# capactive_hub.net
KiCad netlist of a schematic drawn in EAGLE
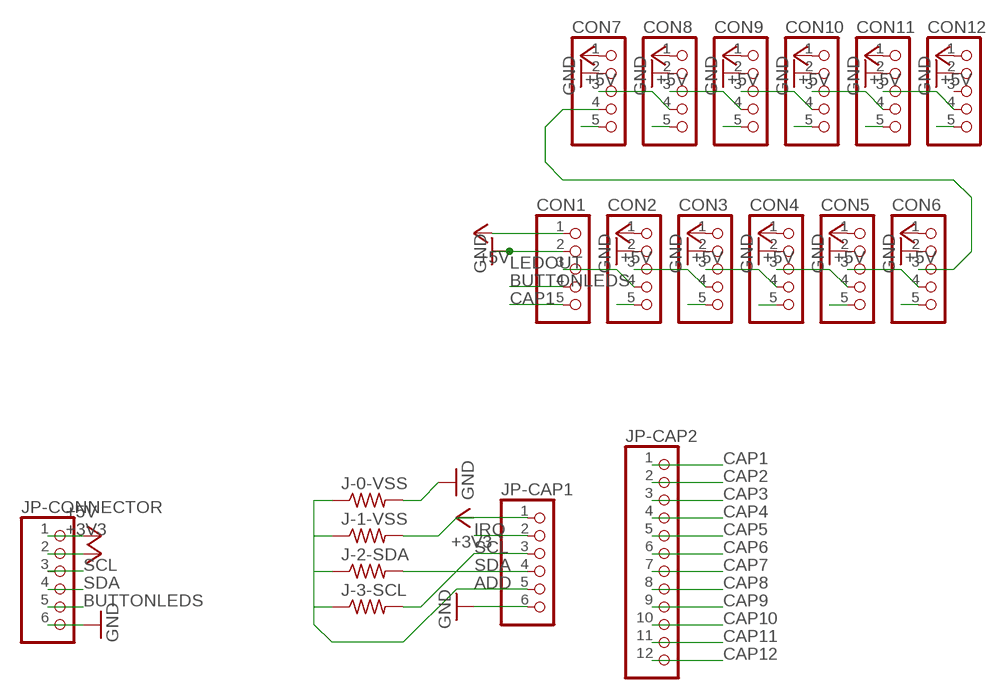
[diagram p0: schematic, sheet 1]

(export (version "E")
  (design (tool "Eeschema 10.0.6"))
  (components
    (comp (ref "CON1")
      (value "PINHD-1X5")
      (footprint "eagle-import:1X05")
      (libsource (lib "eagle-import") (part "PINHD-1X5"))
    )
    (comp (ref "CON2")
      (value "PINHD-1X5")
      (footprint "eagle-import:1X05")
      (libsource (lib "eagle-import") (part "PINHD-1X5"))
    )
    (comp (ref "CON3")
      (value "PINHD-1X5")
      (footprint "eagle-import:1X05")
      (libsource (lib "eagle-import") (part "PINHD-1X5"))
    )
    (comp (ref "CON4")
      (value "PINHD-1X5")
      (footprint "eagle-import:1X05")
      (libsource (lib "eagle-import") (part "PINHD-1X5"))
    )
    (comp (ref "CON5")
      (value "PINHD-1X5")
      (footprint "eagle-import:1X05")
      (libsource (lib "eagle-import") (part "PINHD-1X5"))
    )
    (comp (ref "CON6")
      (value "PINHD-1X5")
      (footprint "eagle-import:1X05")
      (libsource (lib "eagle-import") (part "PINHD-1X5"))
    )
    (comp (ref "CON7")
      (value "PINHD-1X5")
      (footprint "eagle-import:1X05")
      (libsource (lib "eagle-import") (part "PINHD-1X5"))
    )
    (comp (ref "CON8")
      (value "PINHD-1X5")
      (footprint "eagle-import:1X05")
      (libsource (lib "eagle-import") (part "PINHD-1X5"))
    )
    (comp (ref "CON9")
      (value "PINHD-1X5")
      (footprint "eagle-import:1X05")
      (libsource (lib "eagle-import") (part "PINHD-1X5"))
    )
    (comp (ref "CON10")
      (value "PINHD-1X5")
      (footprint "eagle-import:1X05")
      (libsource (lib "eagle-import") (part "PINHD-1X5"))
    )
    (comp (ref "CON11")
      (value "PINHD-1X5")
      (footprint "eagle-import:1X05")
      (libsource (lib "eagle-import") (part "PINHD-1X5"))
    )
    (comp (ref "CON12")
      (value "PINHD-1X5")
      (footprint "eagle-import:1X05")
      (libsource (lib "eagle-import") (part "PINHD-1X5"))
    )
    (comp (ref "J-0-VSS")
      (value "RES-US1206FAB")
      (footprint "eagle-import:R1206FAB")
      (libsource (lib "eagle-import") (part "RES-US1206FAB"))
    )
    (comp (ref "J-1-VSS")
      (value "RES-US1206FAB")
      (footprint "eagle-import:R1206FAB")
      (libsource (lib "eagle-import") (part "RES-US1206FAB"))
    )
    (comp (ref "J-2-SDA")
      (value "RES-US1206FAB")
      (footprint "eagle-import:R1206FAB")
      (libsource (lib "eagle-import") (part "RES-US1206FAB"))
    )
    (comp (ref "J-3-SCL")
      (value "RES-US1206FAB")
      (footprint "eagle-import:R1206FAB")
      (libsource (lib "eagle-import") (part "RES-US1206FAB"))
    )
    (comp (ref "JP-CAP1")
      (value "PINHD-1X6")
      (footprint "eagle-import:1X06")
      (libsource (lib "eagle-import") (part "PINHD-1X6"))
    )
    (comp (ref "JP-CAP2")
      (value "PINHD-1X12")
      (footprint "eagle-import:1X12")
      (libsource (lib "eagle-import") (part "PINHD-1X12"))
    )
    (comp (ref "JP-CONNECTOR")
      (value "PINHD-1X6")
      (footprint "eagle-import:1X06")
      (libsource (lib "eagle-import") (part "PINHD-1X6"))
    )
  )
  (nets
    (net (code "1") (name "+3V3") (class "Default")
      (node (ref "J-1-VSS") (pin "2") (pinfunction "2_2") (pintype "passive"))
      (node (ref "JP-CAP1") (pin "1") (pinfunction "1_1") (pintype "passive"))
      (node (ref "JP-CONNECTOR") (pin "2") (pinfunction "2_2") (pintype "passive"))
    )
    (net (code "2") (name "+5V") (class "Default")
      (node (ref "CON1") (pin "1") (pinfunction "1_1") (pintype "passive"))
      (node (ref "CON10") (pin "1") (pinfunction "1_1") (pintype "passive"))
      (node (ref "CON11") (pin "1") (pinfunction "1_1") (pintype "passive"))
      (node (ref "CON12") (pin "1") (pinfunction "1_1") (pintype "passive"))
      (node (ref "CON2") (pin "1") (pinfunction "1_1") (pintype "passive"))
      (node (ref "CON3") (pin "1") (pinfunction "1_1") (pintype "passive"))
      (node (ref "CON4") (pin "1") (pinfunction "1_1") (pintype "passive"))
      (node (ref "CON5") (pin "1") (pinfunction "1_1") (pintype "passive"))
      (node (ref "CON6") (pin "1") (pinfunction "1_1") (pintype "passive"))
      (node (ref "CON7") (pin "1") (pinfunction "1_1") (pintype "passive"))
      (node (ref "CON8") (pin "1") (pinfunction "1_1") (pintype "passive"))
      (node (ref "CON9") (pin "1") (pinfunction "1_1") (pintype "passive"))
      (node (ref "JP-CONNECTOR") (pin "1") (pinfunction "1_1") (pintype "passive"))
    )
    (net (code "3") (name "/ADD") (class "Default")
      (node (ref "J-0-VSS") (pin "1") (pinfunction "1_1") (pintype "passive"))
      (node (ref "J-1-VSS") (pin "1") (pinfunction "1_1") (pintype "passive"))
      (node (ref "J-2-SDA") (pin "1") (pinfunction "1_1") (pintype "passive"))
      (node (ref "J-3-SCL") (pin "1") (pinfunction "1_1") (pintype "passive"))
      (node (ref "JP-CAP1") (pin "5") (pinfunction "5_5") (pintype "passive"))
    )
    (net (code "4") (name "/BUTTONLEDS") (class "Default")
      (node (ref "CON1") (pin "4") (pinfunction "4_4") (pintype "passive"))
      (node (ref "JP-CONNECTOR") (pin "5") (pinfunction "5_5") (pintype "passive"))
    )
    (net (code "5") (name "/CAP1") (class "Default")
      (node (ref "CON1") (pin "5") (pinfunction "5_5") (pintype "passive"))
      (node (ref "JP-CAP2") (pin "1") (pinfunction "1_1") (pintype "passive"))
    )
    (net (code "6") (name "/CAP2") (class "Default")
      (node (ref "CON2") (pin "5") (pinfunction "5_5") (pintype "passive"))
      (node (ref "JP-CAP2") (pin "2") (pinfunction "2_2") (pintype "passive"))
    )
    (net (code "7") (name "/CAP3") (class "Default")
      (node (ref "CON3") (pin "5") (pinfunction "5_5") (pintype "passive"))
      (node (ref "JP-CAP2") (pin "3") (pinfunction "3_3") (pintype "passive"))
    )
    (net (code "8") (name "/CAP4") (class "Default")
      (node (ref "CON4") (pin "5") (pinfunction "5_5") (pintype "passive"))
      (node (ref "JP-CAP2") (pin "4") (pinfunction "4_4") (pintype "passive"))
    )
    (net (code "9") (name "/CAP5") (class "Default")
      (node (ref "CON5") (pin "5") (pinfunction "5_5") (pintype "passive"))
      (node (ref "JP-CAP2") (pin "5") (pinfunction "5_5") (pintype "passive"))
    )
    (net (code "10") (name "/CAP6") (class "Default")
      (node (ref "CON6") (pin "5") (pinfunction "5_5") (pintype "passive"))
      (node (ref "JP-CAP2") (pin "6") (pinfunction "6_6") (pintype "passive"))
    )
    (net (code "11") (name "/CAP7") (class "Default")
      (node (ref "CON7") (pin "5") (pinfunction "5_5") (pintype "passive"))
      (node (ref "JP-CAP2") (pin "7") (pinfunction "7_7") (pintype "passive"))
    )
    (net (code "12") (name "/CAP8") (class "Default")
      (node (ref "CON8") (pin "5") (pinfunction "5_5") (pintype "passive"))
      (node (ref "JP-CAP2") (pin "8") (pinfunction "8_8") (pintype "passive"))
    )
    (net (code "13") (name "/CAP9") (class "Default")
      (node (ref "CON9") (pin "5") (pinfunction "5_5") (pintype "passive"))
      (node (ref "JP-CAP2") (pin "9") (pinfunction "9_9") (pintype "passive"))
    )
    (net (code "14") (name "/CAP10") (class "Default")
      (node (ref "CON10") (pin "5") (pinfunction "5_5") (pintype "passive"))
      (node (ref "JP-CAP2") (pin "10") (pinfunction "10_10") (pintype "passive"))
    )
    (net (code "15") (name "/CAP11") (class "Default")
      (node (ref "CON11") (pin "5") (pinfunction "5_5") (pintype "passive"))
      (node (ref "JP-CAP2") (pin "11") (pinfunction "11_11") (pintype "passive"))
    )
    (net (code "16") (name "/CAP12") (class "Default")
      (node (ref "CON12") (pin "5") (pinfunction "5_5") (pintype "passive"))
      (node (ref "JP-CAP2") (pin "12") (pinfunction "12_12") (pintype "passive"))
    )
    (net (code "17") (name "/IRQ") (class "Default")
      (node (ref "JP-CAP1") (pin "2") (pinfunction "2_2") (pintype "passive"))
    )
    (net (code "18") (name "/LEDOUT") (class "Default")
      (node (ref "CON1") (pin "3") (pinfunction "3_3") (pintype "passive"))
      (node (ref "CON2") (pin "4") (pinfunction "4_4") (pintype "passive"))
    )
    (net (code "19") (name "/SCL") (class "Default")
      (node (ref "J-3-SCL") (pin "2") (pinfunction "2_2") (pintype "passive"))
      (node (ref "JP-CAP1") (pin "3") (pinfunction "3_3") (pintype "passive"))
      (node (ref "JP-CONNECTOR") (pin "3") (pinfunction "3_3") (pintype "passive"))
    )
    (net (code "20") (name "/SDA") (class "Default")
      (node (ref "J-2-SDA") (pin "2") (pinfunction "2_2") (pintype "passive"))
      (node (ref "JP-CAP1") (pin "4") (pinfunction "4_4") (pintype "passive"))
      (node (ref "JP-CONNECTOR") (pin "4") (pinfunction "4_4") (pintype "passive"))
    )
    (net (code "21") (name "GND") (class "Default")
      (node (ref "CON1") (pin "2") (pinfunction "2_2") (pintype "passive"))
      (node (ref "CON10") (pin "2") (pinfunction "2_2") (pintype "passive"))
      (node (ref "CON11") (pin "2") (pinfunction "2_2") (pintype "passive"))
      (node (ref "CON12") (pin "2") (pinfunction "2_2") (pintype "passive"))
      (node (ref "CON2") (pin "2") (pinfunction "2_2") (pintype "passive"))
      (node (ref "CON3") (pin "2") (pinfunction "2_2") (pintype "passive"))
      (node (ref "CON4") (pin "2") (pinfunction "2_2") (pintype "passive"))
      (node (ref "CON5") (pin "2") (pinfunction "2_2") (pintype "passive"))
      (node (ref "CON6") (pin "2") (pinfunction "2_2") (pintype "passive"))
      (node (ref "CON7") (pin "2") (pinfunction "2_2") (pintype "passive"))
      (node (ref "CON8") (pin "2") (pinfunction "2_2") (pintype "passive"))
      (node (ref "CON9") (pin "2") (pinfunction "2_2") (pintype "passive"))
      (node (ref "J-0-VSS") (pin "2") (pinfunction "2_2") (pintype "passive"))
      (node (ref "JP-CAP1") (pin "6") (pinfunction "6_6") (pintype "passive"))
      (node (ref "JP-CONNECTOR") (pin "6") (pinfunction "6_6") (pintype "passive"))
    )
    (net (code "22") (name "Net-(CON2-Pad3)") (class "Default")
      (node (ref "CON2") (pin "3") (pinfunction "3_3") (pintype "passive"))
      (node (ref "CON3") (pin "4") (pinfunction "4_4") (pintype "passive"))
    )
    (net (code "23") (name "Net-(CON3-Pad3)") (class "Default")
      (node (ref "CON3") (pin "3") (pinfunction "3_3") (pintype "passive"))
      (node (ref "CON4") (pin "4") (pinfunction "4_4") (pintype "passive"))
    )
    (net (code "24") (name "Net-(CON4-Pad3)") (class "Default")
      (node (ref "CON4") (pin "3") (pinfunction "3_3") (pintype "passive"))
      (node (ref "CON5") (pin "4") (pinfunction "4_4") (pintype "passive"))
    )
    (net (code "25") (name "Net-(CON5-Pad3)") (class "Default")
      (node (ref "CON5") (pin "3") (pinfunction "3_3") (pintype "passive"))
      (node (ref "CON6") (pin "4") (pinfunction "4_4") (pintype "passive"))
    )
    (net (code "26") (name "Net-(CON6-Pad3)") (class "Default")
      (node (ref "CON6") (pin "3") (pinfunction "3_3") (pintype "passive"))
      (node (ref "CON7") (pin "4") (pinfunction "4_4") (pintype "passive"))
    )
    (net (code "27") (name "Net-(CON7-Pad3)") (class "Default")
      (node (ref "CON7") (pin "3") (pinfunction "3_3") (pintype "passive"))
      (node (ref "CON8") (pin "4") (pinfunction "4_4") (pintype "passive"))
    )
    (net (code "28") (name "Net-(CON8-Pad3)") (class "Default")
      (node (ref "CON8") (pin "3") (pinfunction "3_3") (pintype "passive"))
      (node (ref "CON9") (pin "4") (pinfunction "4_4") (pintype "passive"))
    )
    (net (code "29") (name "Net-(CON10-Pad3)") (class "Default")
      (node (ref "CON10") (pin "3") (pinfunction "3_3") (pintype "passive"))
      (node (ref "CON11") (pin "4") (pinfunction "4_4") (pintype "passive"))
    )
    (net (code "30") (name "Net-(CON10-Pad4)") (class "Default")
      (node (ref "CON10") (pin "4") (pinfunction "4_4") (pintype "passive"))
      (node (ref "CON9") (pin "3") (pinfunction "3_3") (pintype "passive"))
    )
    (net (code "31") (name "Net-(CON11-Pad3)") (class "Default")
      (node (ref "CON11") (pin "3") (pinfunction "3_3") (pintype "passive"))
      (node (ref "CON12") (pin "4") (pinfunction "4_4") (pintype "passive"))
    )
    (net (code "32") (name "unconnected-(CON12-Pad3)") (class "Default")
      (node (ref "CON12") (pin "3") (pinfunction "3_3") (pintype "passive"))
    )
  )
)
